# XBee-Explorer-Dongle-Sparkfun.net
KiCad netlist of a schematic drawn in EAGLE
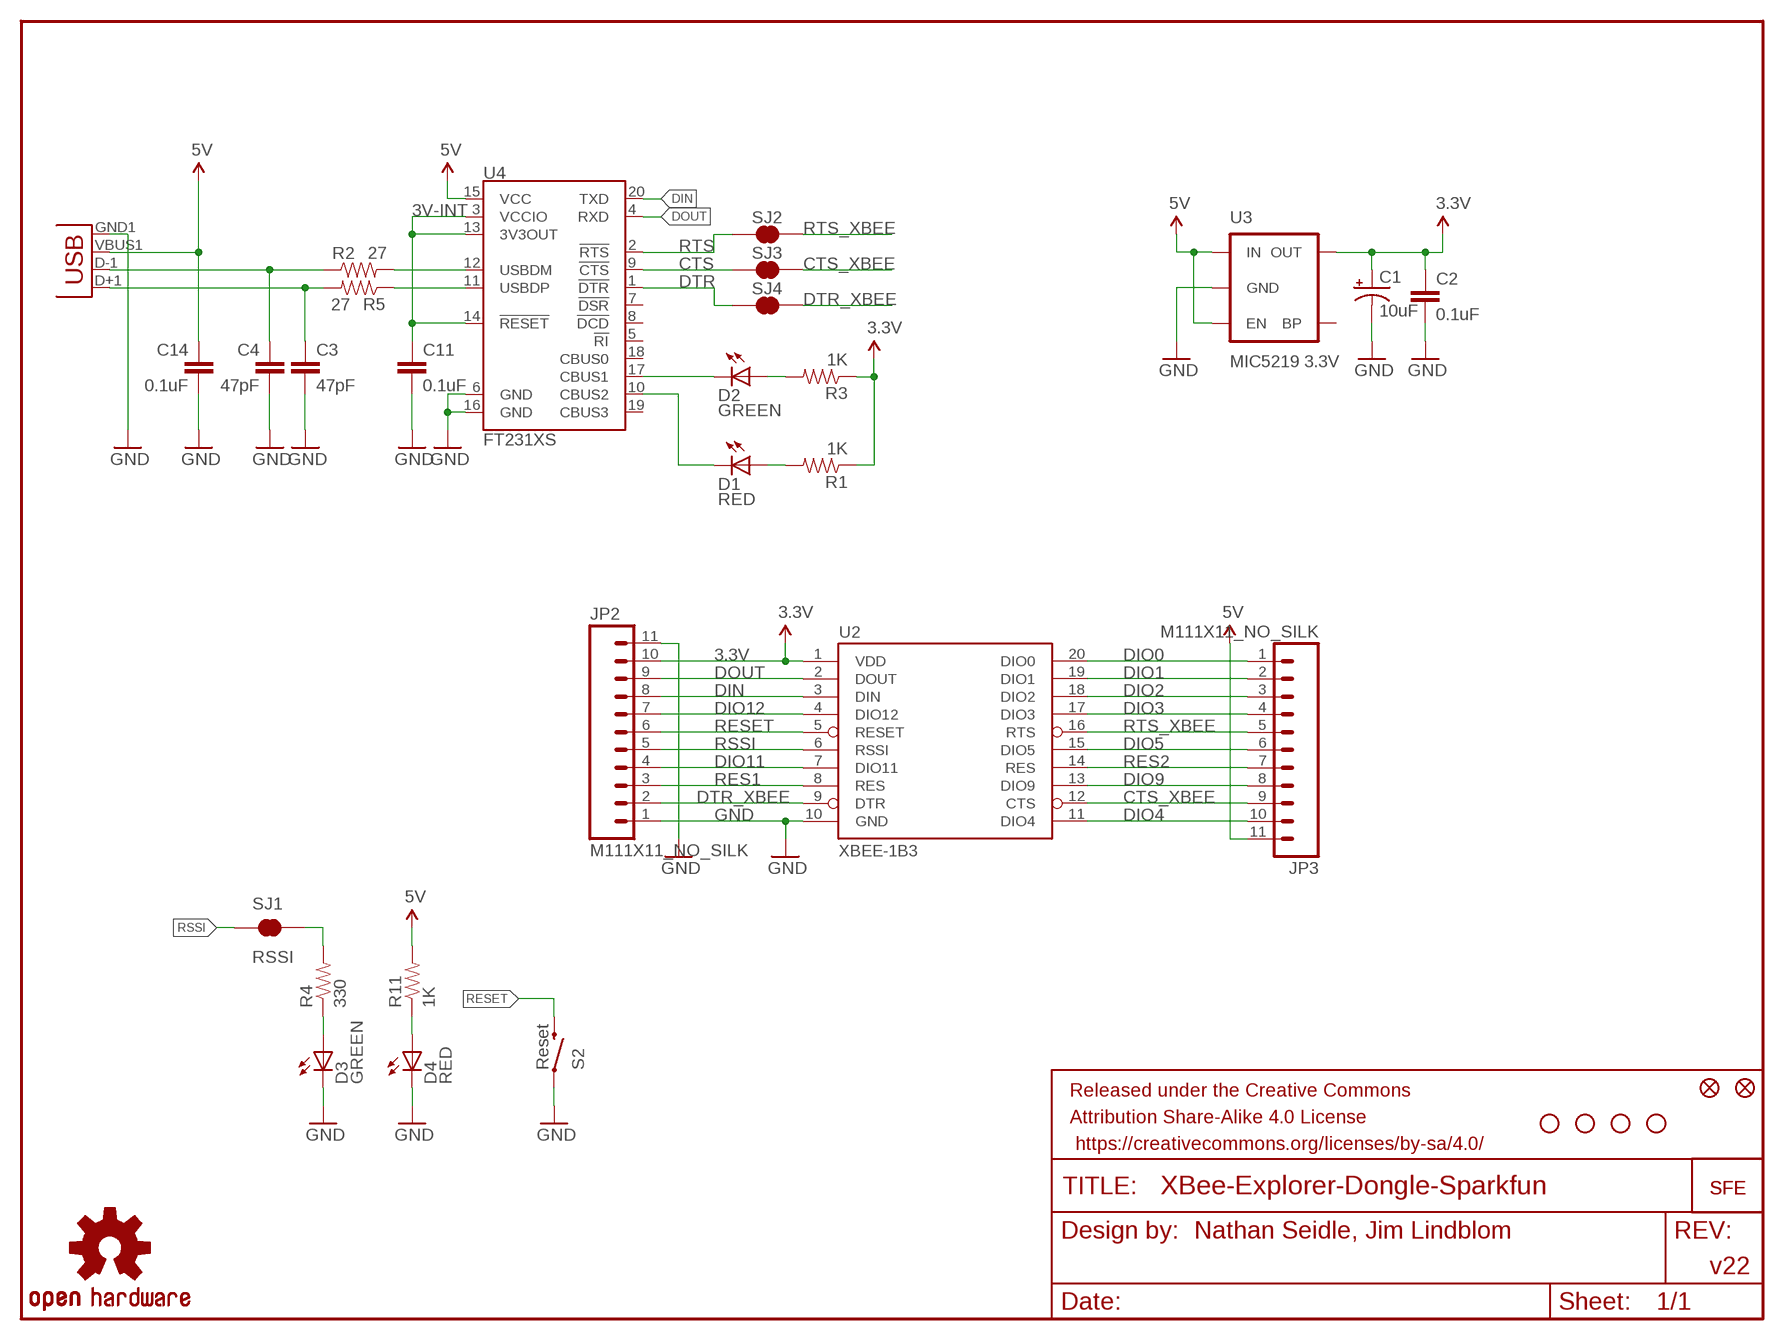
[diagram p0: schematic, sheet 1]

(export (version "E")
  (design (tool "Eeschema 10.0.6"))
  (components
    (comp (ref "C1")
      (value "10uF")
      (footprint "eagle-import:EIA3216")
      (libsource (lib "eagle-import") (part "CAP_POL1206"))
    )
    (comp (ref "C2")
      (value "0.1uF")
      (footprint "eagle-import:0603-CAP")
      (libsource (lib "eagle-import") (part "CAP0603-CAP"))
    )
    (comp (ref "C3")
      (value "47pF")
      (footprint "eagle-import:0603-CAP")
      (libsource (lib "eagle-import") (part "CAP0603-CAP"))
    )
    (comp (ref "C4")
      (value "47pF")
      (footprint "eagle-import:0603-CAP")
      (libsource (lib "eagle-import") (part "CAP0603-CAP"))
    )
    (comp (ref "C11")
      (value "0.1uF")
      (footprint "eagle-import:0603-CAP")
      (libsource (lib "eagle-import") (part "CAP0603-CAP"))
    )
    (comp (ref "C14")
      (value "0.1uF")
      (footprint "eagle-import:0603-CAP")
      (libsource (lib "eagle-import") (part "CAP0603-CAP"))
    )
    (comp (ref "D1")
      (value "RED")
      (footprint "eagle-import:LED-0603")
      (libsource (lib "eagle-import") (part "LED-RED0603"))
    )
    (comp (ref "D2")
      (value "GREEN")
      (footprint "eagle-import:LED-0603")
      (libsource (lib "eagle-import") (part "LED-GREEN0603"))
    )
    (comp (ref "D3")
      (value "GREEN")
      (footprint "eagle-import:LED-0603")
      (libsource (lib "eagle-import") (part "LED-GREEN0603"))
    )
    (comp (ref "D4")
      (value "RED")
      (footprint "eagle-import:LED-0603")
      (libsource (lib "eagle-import") (part "LED-RED0603"))
    )
    (comp (ref "FID1")
      (value "FIDUCIAL1X2")
      (footprint "eagle-import:FIDUCIAL-1X2")
      (libsource (lib "eagle-import") (part "FIDUCIAL1X2"))
    )
    (comp (ref "FID2")
      (value "FIDUCIAL1X2")
      (footprint "eagle-import:FIDUCIAL-1X2")
      (libsource (lib "eagle-import") (part "FIDUCIAL1X2"))
    )
    (comp (ref "FRAME1")
      (value "FRAME-LETTER")
      (footprint "eagle-import:CREATIVE_COMMONS")
      (libsource (lib "eagle-import") (part "FRAME-LETTER"))
    )
    (comp (ref "JP1")
      (value "USBA-SMD-MALE-LOCKING")
      (footprint "eagle-import:USB-A-SMT-MALE-LOCKING")
      (libsource (lib "eagle-import") (part "USBA-SMD-MALE-LOCKING"))
    )
    (comp (ref "JP2")
      (value "M111X11_NO_SILK")
      (footprint "eagle-import:1X11_NO_SILK")
      (libsource (lib "eagle-import") (part "M111X11_NO_SILK"))
    )
    (comp (ref "JP3")
      (value "M111X11_NO_SILK")
      (footprint "eagle-import:1X11_NO_SILK")
      (libsource (lib "eagle-import") (part "M111X11_NO_SILK"))
    )
    (comp (ref "R1")
      (value "1K")
      (footprint "eagle-import:0603-RES")
      (libsource (lib "eagle-import") (part "RESISTOR0603-RES"))
    )
    (comp (ref "R2")
      (value "27")
      (footprint "eagle-import:0603-RES")
      (libsource (lib "eagle-import") (part "RESISTOR0603-RES"))
    )
    (comp (ref "R3")
      (value "1K")
      (footprint "eagle-import:0603-RES")
      (libsource (lib "eagle-import") (part "RESISTOR0603-RES"))
    )
    (comp (ref "R4")
      (value "330")
      (footprint "eagle-import:0603-RES")
      (libsource (lib "eagle-import") (part "RESISTOR0603-RES"))
    )
    (comp (ref "R5")
      (value "27")
      (footprint "eagle-import:0603-RES")
      (libsource (lib "eagle-import") (part "RESISTOR0603-RES"))
    )
    (comp (ref "R11")
      (value "1K")
      (footprint "eagle-import:0603-RES")
      (libsource (lib "eagle-import") (part "RESISTOR0603-RES"))
    )
    (comp (ref "S2")
      (value "Reset")
      (footprint "eagle-import:TACTILE_SWITCH_SMD")
      (libsource (lib "eagle-import") (part "SWITCH-MOMENTARY-2SMD"))
    )
    (comp (ref "SJ1")
      (value "RSSI")
      (footprint "eagle-import:SJ_2S-TRACE")
      (libsource (lib "eagle-import") (part "SOLDERJUMPERTRACE"))
    )
    (comp (ref "SJ2")
      (value "RSSI")
      (footprint "eagle-import:SJ_2S-TRACE")
      (libsource (lib "eagle-import") (part "SOLDERJUMPERTRACE"))
    )
    (comp (ref "SJ3")
      (value "RSSI")
      (footprint "eagle-import:SJ_2S-TRACE")
      (libsource (lib "eagle-import") (part "SOLDERJUMPERTRACE"))
    )
    (comp (ref "SJ4")
      (value "RSSI")
      (footprint "eagle-import:SJ_2S-TRACE")
      (libsource (lib "eagle-import") (part "SOLDERJUMPERTRACE"))
    )
    (comp (ref "U$1")
      (value "LOGO-SFESK")
      (footprint "eagle-import:SFE-LOGO-FLAME")
      (libsource (lib "eagle-import") (part "LOGO-SFESK"))
    )
    (comp (ref "U$4")
      (value "LOGO-SFENEW")
      (footprint "eagle-import:SFE-NEW-WEBLOGO")
      (libsource (lib "eagle-import") (part "LOGO-SFENEW"))
    )
    (comp (ref "U$5")
      (value "STAND-OFF")
      (footprint "eagle-import:STAND-OFF")
      (libsource (lib "eagle-import") (part "STAND-OFF"))
    )
    (comp (ref "U$7")
      (value "OSHW-LOGOS")
      (footprint "eagle-import:OSHW-LOGO-S")
      (libsource (lib "eagle-import") (part "OSHW-LOGOS"))
    )
    (comp (ref "U$9")
      (value "STAND-OFF")
      (footprint "eagle-import:STAND-OFF")
      (libsource (lib "eagle-import") (part "STAND-OFF"))
    )
    (comp (ref "U$10")
      (value "STAND-OFF")
      (footprint "eagle-import:STAND-OFF")
      (libsource (lib "eagle-import") (part "STAND-OFF"))
    )
    (comp (ref "U$11")
      (value "STAND-OFF")
      (footprint "eagle-import:STAND-OFF")
      (libsource (lib "eagle-import") (part "STAND-OFF"))
    )
    (comp (ref "U2")
      (value "XBEE-1B3")
      (footprint "eagle-import:XBEE-SMD")
      (libsource (lib "eagle-import") (part "XBEE-1B3"))
    )
    (comp (ref "U3")
      (value "MIC5219 3.3V")
      (footprint "eagle-import:SOT23-5")
      (libsource (lib "eagle-import") (part "V_REG_LDOSMD"))
    )
    (comp (ref "U4")
      (value "FT231XS")
      (footprint "eagle-import:SSOP20_L")
      (libsource (lib "eagle-import") (part "FT231XS"))
    )
  )
  (nets
    (net (code "1") (name "/3V-INT") (class "Default")
      (node (ref "C11") (pin "1") (pinfunction "1_1") (pintype "passive"))
      (node (ref "U4") (pin "13") (pinfunction "3V3OUT_13") (pintype "bidirectional"))
      (node (ref "U4") (pin "14") (pinfunction "~{RESET}_14") (pintype "bidirectional"))
      (node (ref "U4") (pin "3") (pinfunction "VCCIO_3") (pintype "bidirectional"))
    )
    (net (code "2") (name "/CTS") (class "Default")
      (node (ref "SJ3") (pin "1") (pinfunction "1_1") (pintype "passive"))
      (node (ref "U4") (pin "9") (pinfunction "~{CTS}_9") (pintype "bidirectional"))
    )
    (net (code "3") (name "/CTS_XBEE") (class "Default")
      (node (ref "JP3") (pin "9") (pinfunction "9_9") (pintype "passive"))
      (node (ref "SJ3") (pin "2") (pinfunction "2_2") (pintype "passive"))
      (node (ref "U2") (pin "12") (pinfunction "CTS_12") (pintype "output"))
    )
    (net (code "4") (name "/DIO0") (class "Default")
      (node (ref "JP3") (pin "1") (pinfunction "1_1") (pintype "passive"))
      (node (ref "U2") (pin "20") (pinfunction "DIO0_20") (pintype "bidirectional"))
    )
    (net (code "5") (name "/DIO1") (class "Default")
      (node (ref "JP3") (pin "2") (pinfunction "2_2") (pintype "passive"))
      (node (ref "U2") (pin "19") (pinfunction "DIO1_19") (pintype "bidirectional"))
    )
    (net (code "6") (name "/DIO2") (class "Default")
      (node (ref "JP3") (pin "3") (pinfunction "3_3") (pintype "passive"))
      (node (ref "U2") (pin "18") (pinfunction "DIO2_18") (pintype "bidirectional"))
    )
    (net (code "7") (name "/DIO3") (class "Default")
      (node (ref "JP3") (pin "4") (pinfunction "4_4") (pintype "passive"))
      (node (ref "U2") (pin "17") (pinfunction "DIO3_17") (pintype "bidirectional"))
    )
    (net (code "8") (name "/DIO4") (class "Default")
      (node (ref "JP3") (pin "10") (pinfunction "10_10") (pintype "passive"))
      (node (ref "U2") (pin "11") (pinfunction "DIO4_11") (pintype "bidirectional"))
    )
    (net (code "9") (name "/DIO5") (class "Default")
      (node (ref "JP3") (pin "6") (pinfunction "6_6") (pintype "passive"))
      (node (ref "U2") (pin "15") (pinfunction "DIO5_15") (pintype "bidirectional"))
    )
    (net (code "10") (name "/DIO9") (class "Default")
      (node (ref "JP3") (pin "8") (pinfunction "8_8") (pintype "passive"))
      (node (ref "U2") (pin "13") (pinfunction "DIO9_13") (pintype "bidirectional"))
    )
    (net (code "11") (name "/DIO11") (class "Default")
      (node (ref "JP2") (pin "4") (pinfunction "4_4") (pintype "passive"))
      (node (ref "U2") (pin "7") (pinfunction "DIO11_7") (pintype "bidirectional"))
    )
    (net (code "12") (name "/DIO12") (class "Default")
      (node (ref "JP2") (pin "7") (pinfunction "7_7") (pintype "passive"))
      (node (ref "U2") (pin "4") (pinfunction "DIO12_4") (pintype "bidirectional"))
    )
    (net (code "13") (name "/DTR") (class "Default")
      (node (ref "SJ4") (pin "1") (pinfunction "1_1") (pintype "passive"))
      (node (ref "U4") (pin "1") (pinfunction "~{DTR}_1") (pintype "bidirectional"))
    )
    (net (code "14") (name "/DTR_XBEE") (class "Default")
      (node (ref "JP2") (pin "2") (pinfunction "2_2") (pintype "passive"))
      (node (ref "SJ4") (pin "2") (pinfunction "2_2") (pintype "passive"))
      (node (ref "U2") (pin "9") (pinfunction "DTR_9") (pintype "bidirectional"))
    )
    (net (code "15") (name "/RES1") (class "Default")
      (node (ref "JP2") (pin "3") (pinfunction "3_3") (pintype "passive"))
      (node (ref "U2") (pin "8") (pinfunction "RES_8") (pintype "bidirectional"))
    )
    (net (code "16") (name "/RES2") (class "Default")
      (node (ref "JP3") (pin "7") (pinfunction "7_7") (pintype "passive"))
      (node (ref "U2") (pin "14") (pinfunction "RES_14") (pintype "bidirectional"))
    )
    (net (code "17") (name "/RTS") (class "Default")
      (node (ref "SJ2") (pin "1") (pinfunction "1_1") (pintype "passive"))
      (node (ref "U4") (pin "2") (pinfunction "~{RTS}_2") (pintype "bidirectional"))
    )
    (net (code "18") (name "/RTS_XBEE") (class "Default")
      (node (ref "JP3") (pin "5") (pinfunction "5_5") (pintype "passive"))
      (node (ref "SJ2") (pin "2") (pinfunction "2_2") (pintype "passive"))
      (node (ref "U2") (pin "16") (pinfunction "RTS_16") (pintype "input"))
    )
    (net (code "19") (name "3.3V") (class "Default")
      (node (ref "C1") (pin "A") (pinfunction "+_A") (pintype "passive"))
      (node (ref "C2") (pin "1") (pinfunction "1_1") (pintype "passive"))
      (node (ref "JP2") (pin "10") (pinfunction "10_10") (pintype "passive"))
      (node (ref "R1") (pin "1") (pinfunction "1_1") (pintype "passive"))
      (node (ref "R3") (pin "1") (pinfunction "1_1") (pintype "passive"))
      (node (ref "U2") (pin "1") (pinfunction "VDD_1") (pintype "power_in"))
      (node (ref "U3") (pin "5") (pinfunction "OUT_5") (pintype "passive"))
    )
    (net (code "20") (name "5V") (class "Default")
      (node (ref "C14") (pin "1") (pinfunction "1_1") (pintype "passive"))
      (node (ref "JP1") (pin "VBUS1") (pinfunction "VBUS_VBUS1") (pintype "bidirectional"))
      (node (ref "JP3") (pin "11") (pinfunction "11_11") (pintype "passive"))
      (node (ref "R11") (pin "2") (pinfunction "2_2") (pintype "passive"))
      (node (ref "U3") (pin "1") (pinfunction "IN_1") (pintype "input"))
      (node (ref "U3") (pin "3") (pinfunction "EN_3") (pintype "input"))
      (node (ref "U4") (pin "15") (pinfunction "VCC_15") (pintype "bidirectional"))
    )
    (net (code "21") (name "DIN") (class "Default")
      (node (ref "JP2") (pin "8") (pinfunction "8_8") (pintype "passive"))
      (node (ref "U2") (pin "3") (pinfunction "DIN_3") (pintype "input"))
      (node (ref "U4") (pin "20") (pinfunction "TXD_20") (pintype "bidirectional"))
    )
    (net (code "22") (name "DOUT") (class "Default")
      (node (ref "JP2") (pin "9") (pinfunction "9_9") (pintype "passive"))
      (node (ref "U2") (pin "2") (pinfunction "DOUT_2") (pintype "output"))
      (node (ref "U4") (pin "4") (pinfunction "RXD_4") (pintype "bidirectional"))
    )
    (net (code "23") (name "GND") (class "Default")
      (node (ref "C1") (pin "C") (pinfunction "-_C") (pintype "passive"))
      (node (ref "C11") (pin "2") (pinfunction "2_2") (pintype "passive"))
      (node (ref "C14") (pin "2") (pinfunction "2_2") (pintype "passive"))
      (node (ref "C2") (pin "2") (pinfunction "2_2") (pintype "passive"))
      (node (ref "C3") (pin "2") (pinfunction "2_2") (pintype "passive"))
      (node (ref "C4") (pin "2") (pinfunction "2_2") (pintype "passive"))
      (node (ref "D3") (pin "C") (pinfunction "C_C") (pintype "passive"))
      (node (ref "D4") (pin "C") (pinfunction "C_C") (pintype "passive"))
      (node (ref "JP1") (pin "GND1") (pinfunction "GND_GND1") (pintype "bidirectional"))
      (node (ref "JP2") (pin "1") (pinfunction "1_1") (pintype "passive"))
      (node (ref "JP2") (pin "11") (pinfunction "11_11") (pintype "passive"))
      (node (ref "S2") (pin "1") (pinfunction "1_1") (pintype "passive"))
      (node (ref "U2") (pin "10") (pinfunction "GND_10") (pintype "power_in"))
      (node (ref "U3") (pin "2") (pinfunction "GND_2") (pintype "input"))
      (node (ref "U4") (pin "16") (pinfunction "GND_16") (pintype "bidirectional"))
      (node (ref "U4") (pin "6") (pinfunction "GND_6") (pintype "bidirectional"))
    )
    (net (code "24") (name "Net-(D1-PadA)") (class "Default")
      (node (ref "D1") (pin "A") (pinfunction "A_A") (pintype "passive"))
      (node (ref "R1") (pin "2") (pinfunction "2_2") (pintype "passive"))
    )
    (net (code "25") (name "Net-(D2-PadA)") (class "Default")
      (node (ref "D2") (pin "A") (pinfunction "A_A") (pintype "passive"))
      (node (ref "R3") (pin "2") (pinfunction "2_2") (pintype "passive"))
    )
    (net (code "26") (name "Net-(D3-PadA)") (class "Default")
      (node (ref "D3") (pin "A") (pinfunction "A_A") (pintype "passive"))
      (node (ref "R4") (pin "1") (pinfunction "1_1") (pintype "passive"))
    )
    (net (code "27") (name "Net-(D4-PadA)") (class "Default")
      (node (ref "D4") (pin "A") (pinfunction "A_A") (pintype "passive"))
      (node (ref "R11") (pin "1") (pinfunction "1_1") (pintype "passive"))
    )
    (net (code "28") (name "Net-(JP1-D+)") (class "Default")
      (node (ref "C3") (pin "1") (pinfunction "1_1") (pintype "passive"))
      (node (ref "JP1") (pin "D+1") (pinfunction "D+_D+1") (pintype "bidirectional"))
      (node (ref "R5") (pin "2") (pinfunction "2_2") (pintype "passive"))
    )
    (net (code "29") (name "Net-(JP1-D-)") (class "Default")
      (node (ref "C4") (pin "1") (pinfunction "1_1") (pintype "passive"))
      (node (ref "JP1") (pin "D-1") (pinfunction "D-_D-1") (pintype "bidirectional"))
      (node (ref "R2") (pin "1") (pinfunction "1_1") (pintype "passive"))
    )
    (net (code "30") (name "Net-(R4-Pad2)") (class "Default")
      (node (ref "R4") (pin "2") (pinfunction "2_2") (pintype "passive"))
      (node (ref "SJ1") (pin "2") (pinfunction "2_2") (pintype "passive"))
    )
    (net (code "31") (name "Net-(U4-CBUS1)") (class "Default")
      (node (ref "D2") (pin "C") (pinfunction "C_C") (pintype "passive"))
      (node (ref "U4") (pin "17") (pinfunction "CBUS1_17") (pintype "bidirectional"))
    )
    (net (code "32") (name "Net-(U4-CBUS2)") (class "Default")
      (node (ref "D1") (pin "C") (pinfunction "C_C") (pintype "passive"))
      (node (ref "U4") (pin "10") (pinfunction "CBUS2_10") (pintype "bidirectional"))
    )
    (net (code "33") (name "Net-(U4-USBDM)") (class "Default")
      (node (ref "R2") (pin "2") (pinfunction "2_2") (pintype "passive"))
      (node (ref "U4") (pin "12") (pinfunction "USBDM_12") (pintype "bidirectional"))
    )
    (net (code "34") (name "Net-(U4-USBDP)") (class "Default")
      (node (ref "R5") (pin "1") (pinfunction "1_1") (pintype "passive"))
      (node (ref "U4") (pin "11") (pinfunction "USBDP_11") (pintype "bidirectional"))
    )
    (net (code "35") (name "RESET") (class "Default")
      (node (ref "JP2") (pin "6") (pinfunction "6_6") (pintype "passive"))
      (node (ref "S2") (pin "3") (pinfunction "2_3") (pintype "passive"))
      (node (ref "U2") (pin "5") (pinfunction "RESET_5") (pintype "input"))
    )
    (net (code "36") (name "RSSI") (class "Default")
      (node (ref "JP2") (pin "5") (pinfunction "5_5") (pintype "passive"))
      (node (ref "SJ1") (pin "1") (pinfunction "1_1") (pintype "passive"))
      (node (ref "U2") (pin "6") (pinfunction "RSSI_6") (pintype "bidirectional"))
    )
    (net (code "37") (name "unconnected-(U3-BP-Pad4)") (class "Default")
      (node (ref "U3") (pin "4") (pinfunction "BP_4") (pintype "input"))
    )
    (net (code "38") (name "unconnected-(U4-CBUS0-Pad18)") (class "Default")
      (node (ref "U4") (pin "18") (pinfunction "CBUS0_18") (pintype "bidirectional"))
    )
    (net (code "39") (name "unconnected-(U4-CBUS3-Pad19)") (class "Default")
      (node (ref "U4") (pin "19") (pinfunction "CBUS3_19") (pintype "bidirectional"))
    )
    (net (code "40") (name "unconnected-(U4-~{DCD}-Pad8)") (class "Default")
      (node (ref "U4") (pin "8") (pinfunction "~{DCD}_8") (pintype "bidirectional"))
    )
    (net (code "41") (name "unconnected-(U4-~{DSR}-Pad7)") (class "Default")
      (node (ref "U4") (pin "7") (pinfunction "~{DSR}_7") (pintype "bidirectional"))
    )
    (net (code "42") (name "unconnected-(U4-~{RI}-Pad5)") (class "Default")
      (node (ref "U4") (pin "5") (pinfunction "~{RI}_5") (pintype "bidirectional"))
    )
  )
)
